# Sheet1.net
KiCad netlist of a schematic drawn in Altium Designer
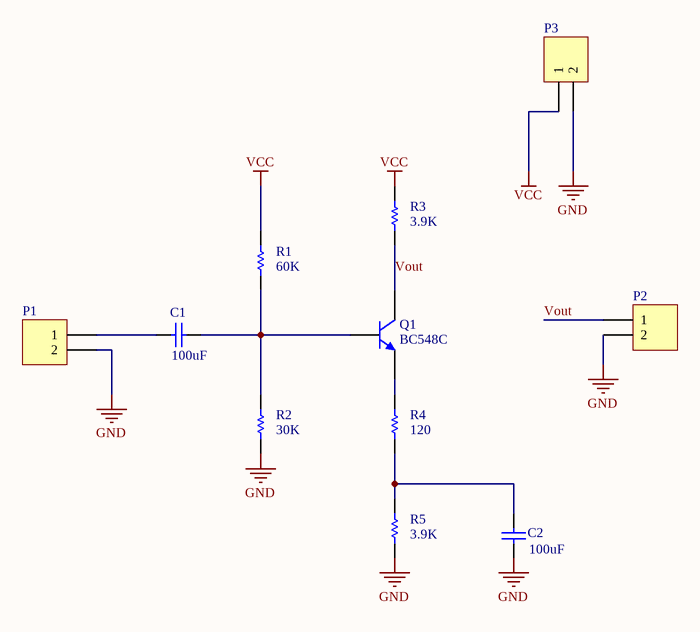
[diagram p0: Sheet1.SchDoc]

(export (version "E")
  (design (tool "Eeschema 10.0.6"))
  (components
    (comp (ref "C1")
      (value "100uF")
      (footprint "RAD-0.3")
      (description "Capacitor")
      (fields (field (name "Comment") "Cap") (field (name "PUBLISHER") "Altium Limited"))
      (libsource (lib "Miscellaneous Devices") (part "Cap"))
    )
    (comp (ref "C2")
      (value "100uF")
      (footprint "RAD-0.3")
      (description "Capacitor")
      (fields (field (name "Comment") "Cap") (field (name "PUBLISHER") "Altium Limited"))
      (libsource (lib "Miscellaneous Devices") (part "Cap"))
    )
    (comp (ref "P1")
      (value "Header 2H")
      (footprint "HDR1X2H")
      (description "Header, 2-Pin, Right Angle")
      (fields (field (name "PUBLISHER") "Altium Limited"))
      (libsource (lib "") (part "Header 2H_2"))
    )
    (comp (ref "P2")
      (value "Header 2H")
      (footprint "HDR1X2H")
      (description "Header, 2-Pin, Right Angle")
      (fields (field (name "PUBLISHER") "Altium Limited"))
      (libsource (lib "Miscellaneous Connectors") (part "Header 2H"))
    )
    (comp (ref "P3")
      (value "Header 2H")
      (footprint "HDR1X2H")
      (description "Header, 2-Pin, Right Angle")
      (fields (field (name "PUBLISHER") "Altium Limited"))
      (libsource (lib "") (part "Header 2H_1"))
    )
    (comp (ref "Q1")
      (value "BC548C")
      (footprint "29-04")
      (description "Amplifier Transistor NPN Silicon")
      (fields (field (name "PUBLISHER") "Altium Limited"))
      (libsource (lib "Motorola Discrete BJT") (part "BC548C"))
    )
    (comp (ref "R1")
      (value "60K")
      (footprint "AXIAL-0.3")
      (description "Resistor")
      (fields (field (name "Comment") "Res1") (field (name "PUBLISHER") "Altium Limited"))
      (libsource (lib "Miscellaneous Devices") (part "Res1"))
    )
    (comp (ref "R2")
      (value "30K")
      (footprint "AXIAL-0.3")
      (description "Resistor")
      (fields (field (name "Comment") "Res1") (field (name "PUBLISHER") "Altium Limited"))
      (libsource (lib "Miscellaneous Devices") (part "Res1"))
    )
    (comp (ref "R3")
      (value "3.9K")
      (footprint "AXIAL-0.3")
      (description "Resistor")
      (fields (field (name "Comment") "Res1") (field (name "PUBLISHER") "Altium Limited"))
      (libsource (lib "Miscellaneous Devices") (part "Res1"))
    )
    (comp (ref "R4")
      (value "120")
      (footprint "AXIAL-0.3")
      (description "Resistor")
      (fields (field (name "Comment") "Res1") (field (name "PUBLISHER") "Altium Limited"))
      (libsource (lib "Miscellaneous Devices") (part "Res1"))
    )
    (comp (ref "R5")
      (value "3.9K")
      (footprint "AXIAL-0.3")
      (description "Resistor")
      (fields (field (name "Comment") "Res1") (field (name "PUBLISHER") "Altium Limited"))
      (libsource (lib "Miscellaneous Devices") (part "Res1"))
    )
  )
  (nets
    (net (code "1") (name "/Vout") (class "Default")
      (node (ref "P2") (pin "1") (pinfunction "1_1") (pintype "passive"))
      (node (ref "Q1") (pin "1") (pinfunction "C_1") (pintype "passive"))
      (node (ref "R3") (pin "1") (pinfunction "1_1") (pintype "passive"))
    )
    (net (code "2") (name "GND") (class "Default")
      (node (ref "C2") (pin "1") (pinfunction "1_1") (pintype "passive"))
      (node (ref "P1") (pin "2") (pinfunction "2_2") (pintype "passive"))
      (node (ref "P2") (pin "2") (pinfunction "2_2") (pintype "passive"))
      (node (ref "P3") (pin "2") (pinfunction "2_2") (pintype "passive"))
      (node (ref "R2") (pin "1") (pinfunction "1_1") (pintype "passive"))
      (node (ref "R5") (pin "1") (pinfunction "1_1") (pintype "passive"))
    )
    (net (code "3") (name "Net-(C1-Pad1)") (class "Default")
      (node (ref "C1") (pin "1") (pinfunction "1_1") (pintype "passive"))
      (node (ref "P1") (pin "1") (pinfunction "1_1") (pintype "passive"))
    )
    (net (code "4") (name "Net-(C2-Pad2)") (class "Default")
      (node (ref "C2") (pin "2") (pinfunction "2_2") (pintype "passive"))
      (node (ref "R4") (pin "1") (pinfunction "1_1") (pintype "passive"))
      (node (ref "R5") (pin "2") (pinfunction "2_2") (pintype "passive"))
    )
    (net (code "5") (name "Net-(Q1-B)") (class "Default")
      (node (ref "C1") (pin "2") (pinfunction "2_2") (pintype "passive"))
      (node (ref "Q1") (pin "2") (pinfunction "B_2") (pintype "passive"))
      (node (ref "R1") (pin "1") (pinfunction "1_1") (pintype "passive"))
      (node (ref "R2") (pin "2") (pinfunction "2_2") (pintype "passive"))
    )
    (net (code "6") (name "Net-(Q1-E)") (class "Default")
      (node (ref "Q1") (pin "3") (pinfunction "E_3") (pintype "passive"))
      (node (ref "R4") (pin "2") (pinfunction "2_2") (pintype "passive"))
    )
    (net (code "7") (name "VCC") (class "Default")
      (node (ref "P3") (pin "1") (pinfunction "1_1") (pintype "passive"))
      (node (ref "R1") (pin "2") (pinfunction "2_2") (pintype "passive"))
      (node (ref "R3") (pin "2") (pinfunction "2_2") (pintype "passive"))
    )
  )
)
